# RXMIX.net
KiCad netlist of a schematic drawn in Altium Designer
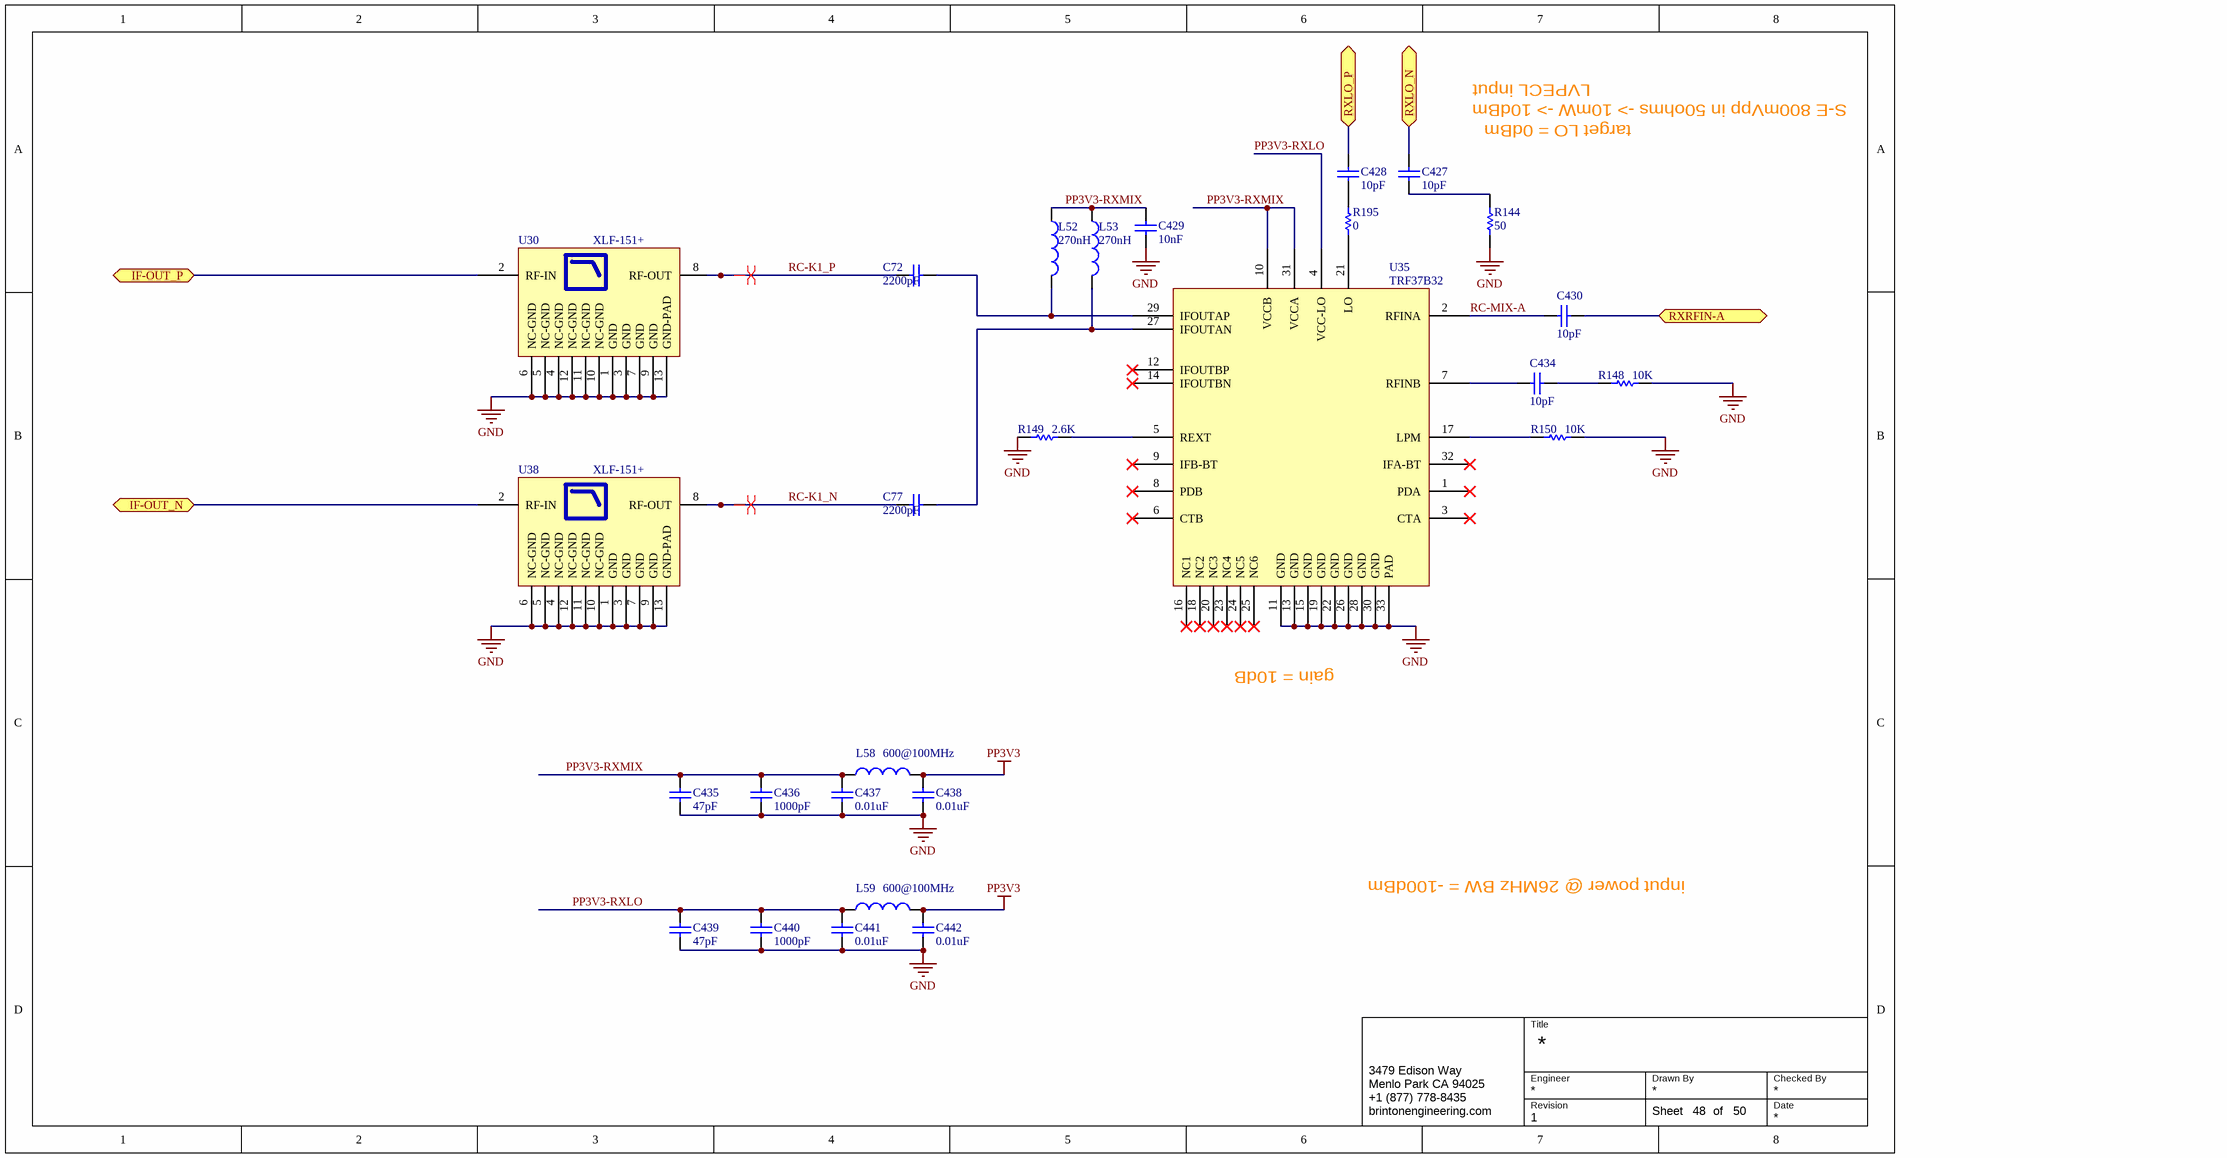
[diagram p0: RXMIX.SchDoc]

(export (version "E")
  (design (tool "Eeschema 10.0.6"))
  (components
    (comp (ref "C72")
      (value "2200pF")
      (footprint "0402")
      (description "CAP 0402")
      (fields (field (name "VOLTAGE") "50V") (field (name "MANUFACTURER") "Kemet"))
      (libsource (lib "PopRock") (part "CAP 0402"))
    )
    (comp (ref "C77")
      (value "2200pF")
      (footprint "0402")
      (description "CAP 0402")
      (fields (field (name "VOLTAGE") "50V") (field (name "MANUFACTURER") "Kemet"))
      (libsource (lib "PopRock") (part "CAP 0402"))
    )
    (comp (ref "C427")
      (value "10pF")
      (footprint "0402")
      (description "CAP 0402")
      (fields (field (name "VOLTAGE") "16V"))
      (libsource (lib "Graviton") (part "CAP 0402"))
    )
    (comp (ref "C428")
      (value "10pF")
      (footprint "0402")
      (description "CAP 0402")
      (fields (field (name "VOLTAGE") "16V"))
      (libsource (lib "Graviton") (part "CAP 0402"))
    )
    (comp (ref "C429")
      (value "10nF")
      (footprint "0402")
      (description "CAP 0402")
      (fields (field (name "VOLTAGE") "16V"))
      (libsource (lib "Graviton") (part "CAP 0402"))
    )
    (comp (ref "C430")
      (value "10pF")
      (footprint "0402")
      (description "CAP 0402")
      (fields (field (name "VOLTAGE") "16V"))
      (libsource (lib "Graviton") (part "CAP 0402"))
    )
    (comp (ref "C434")
      (value "10pF")
      (footprint "0402")
      (description "CAP 0402")
      (fields (field (name "VOLTAGE") "16V"))
      (libsource (lib "Graviton") (part "CAP 0402"))
    )
    (comp (ref "C435")
      (value "47pF")
      (footprint "0402")
      (description "CAP 0402")
      (fields (field (name "VOLTAGE") "25V") (field (name "MANUFACTURER") "Kemet"))
      (libsource (lib "Graviton") (part "CAP 0402"))
    )
    (comp (ref "C436")
      (value "1000pF")
      (footprint "0402")
      (description "CAP 0402")
      (fields (field (name "VOLTAGE") "50V") (field (name "MANUFACTURER") "Murata"))
      (libsource (lib "Graviton") (part "CAP 0402"))
    )
    (comp (ref "C437")
      (value "0.01uF")
      (footprint "0402")
      (description "CAP 0402")
      (fields (field (name "VOLTAGE") "25V") (field (name "MANUFACTURER") "Murata"))
      (libsource (lib "Graviton") (part "CAP 0402"))
    )
    (comp (ref "C438")
      (value "0.01uF")
      (footprint "0402")
      (description "CAP 0402")
      (fields (field (name "VOLTAGE") "25V") (field (name "MANUFACTURER") "Murata"))
      (libsource (lib "Graviton") (part "CAP 0402"))
    )
    (comp (ref "C439")
      (value "47pF")
      (footprint "0402")
      (description "CAP 0402")
      (fields (field (name "VOLTAGE") "25V") (field (name "MANUFACTURER") "Kemet"))
      (libsource (lib "Graviton") (part "CAP 0402"))
    )
    (comp (ref "C440")
      (value "1000pF")
      (footprint "0402")
      (description "CAP 0402")
      (fields (field (name "VOLTAGE") "50V") (field (name "MANUFACTURER") "Murata"))
      (libsource (lib "Graviton") (part "CAP 0402"))
    )
    (comp (ref "C441")
      (value "0.01uF")
      (footprint "0402")
      (description "CAP 0402")
      (fields (field (name "VOLTAGE") "25V") (field (name "MANUFACTURER") "Murata"))
      (libsource (lib "Graviton") (part "CAP 0402"))
    )
    (comp (ref "C442")
      (value "0.01uF")
      (footprint "0402")
      (description "CAP 0402")
      (fields (field (name "VOLTAGE") "25V") (field (name "MANUFACTURER") "Murata"))
      (libsource (lib "Graviton") (part "CAP 0402"))
    )
    (comp (ref "L52")
      (value "270nH")
      (footprint "0603")
      (description "Inductor")
      (fields (field (name "Comment") "IND 0603"))
      (libsource (lib "Graviton") (part "IND 0603"))
    )
    (comp (ref "L53")
      (value "270nH")
      (footprint "0603")
      (description "Inductor")
      (fields (field (name "Comment") "IND 0603"))
      (libsource (lib "Graviton") (part "IND 0603"))
    )
    (comp (ref "L58")
      (value "600@100MHz")
      (footprint "0402")
      (description "Inductor")
      (fields (field (name "MANUFACTURER") "Murata") (field (name "Comment") "IND 0402"))
      (libsource (lib "Graviton") (part "IND 0402"))
    )
    (comp (ref "L59")
      (value "600@100MHz")
      (footprint "0402")
      (description "Inductor")
      (fields (field (name "MANUFACTURER") "Murata") (field (name "Comment") "IND 0402"))
      (libsource (lib "Graviton") (part "IND 0402"))
    )
    (comp (ref "R144")
      (value "50")
      (footprint "0402")
      (description "Resistor, SMD 0402")
      (fields (field (name "Comment") "RES 0402"))
      (libsource (lib "Graviton") (part "RES 0402"))
    )
    (comp (ref "R148")
      (value "10K")
      (footprint "0402")
      (description "Resistor, SMD 0402")
      (fields (field (name "Comment") "RES 0402"))
      (libsource (lib "Graviton") (part "RES 0402"))
    )
    (comp (ref "R149")
      (value "2.6K")
      (footprint "0402")
      (description "Resistor, SMD 0402")
      (fields (field (name "Comment") "RES 0402"))
      (libsource (lib "Graviton") (part "RES 0402"))
    )
    (comp (ref "R150")
      (value "10K")
      (footprint "0402")
      (description "Resistor, SMD 0402")
      (fields (field (name "Comment") "RES 0402"))
      (libsource (lib "Graviton") (part "RES 0402"))
    )
    (comp (ref "R195")
      (value "0")
      (footprint "0402")
      (description "Resistor, SMD 0402")
      (fields (field (name "Comment") "RES 0402"))
      (libsource (lib "Graviton") (part "RES 0402"))
    )
    (comp (ref "U30")
      (value "XLF-151+")
      (footprint "QFN-XLF-12")
      (description "Reflectionless Low-Pass Filter, DC-150Mhz")
      (fields (field (name "MANUFACTURER") "Mini-Circuits"))
      (libsource (lib "Mini-Circuits") (part "XLF-151+"))
    )
    (comp (ref "U35")
      (value "TRF37B32")
      (footprint "RTV-WQFN-32")
      (description "Dual Downmixer,  500-3300MHz with IF Amp")
      (fields (field (name "MANUFACTURER") "Texas Instruments"))
      (libsource (lib "ti") (part "TRF37B32"))
    )
    (comp (ref "U38")
      (value "XLF-151+")
      (footprint "QFN-XLF-12")
      (description "Reflectionless Low-Pass Filter, DC-150Mhz")
      (fields (field (name "MANUFACTURER") "Mini-Circuits"))
      (libsource (lib "Mini-Circuits") (part "XLF-151+"))
    )
  )
  (nets
    (net (code "1") (name "/IF-OUT_N") (class "Default")
      (node (ref "U38") (pin "2") (pinfunction "RF-IN_2") (pintype "passive"))
    )
    (net (code "2") (name "/IF-OUT_P") (class "Default")
      (node (ref "U30") (pin "2") (pinfunction "RF-IN_2") (pintype "passive"))
    )
    (net (code "3") (name "/PP3V3-RXLO") (class "Default")
      (node (ref "C439") (pin "2") (pinfunction "2_2") (pintype "passive"))
      (node (ref "C440") (pin "2") (pinfunction "2_2") (pintype "passive"))
      (node (ref "C441") (pin "2") (pinfunction "2_2") (pintype "passive"))
      (node (ref "L59") (pin "2") (pinfunction "2_2") (pintype "passive"))
      (node (ref "U35") (pin "4") (pinfunction "VCC-LO_4") (pintype "passive"))
    )
    (net (code "4") (name "/PP3V3-RXMIX") (class "Default")
      (node (ref "C429") (pin "2") (pinfunction "2_2") (pintype "passive"))
      (node (ref "C435") (pin "2") (pinfunction "2_2") (pintype "passive"))
      (node (ref "C436") (pin "2") (pinfunction "2_2") (pintype "passive"))
      (node (ref "C437") (pin "2") (pinfunction "2_2") (pintype "passive"))
      (node (ref "L52") (pin "2") (pinfunction "2_2") (pintype "passive"))
      (node (ref "L53") (pin "2") (pinfunction "2_2") (pintype "passive"))
      (node (ref "L58") (pin "2") (pinfunction "2_2") (pintype "passive"))
      (node (ref "U35") (pin "10") (pinfunction "VCCB_10") (pintype "passive"))
      (node (ref "U35") (pin "31") (pinfunction "VCCA_31") (pintype "passive"))
    )
    (net (code "5") (name "/RC-K1_N") (class "Default")
      (node (ref "C77") (pin "2") (pinfunction "2_2") (pintype "passive"))
      (node (ref "U38") (pin "8") (pinfunction "RF-OUT_8") (pintype "passive"))
    )
    (net (code "6") (name "/RC-K1_P") (class "Default")
      (node (ref "C72") (pin "2") (pinfunction "2_2") (pintype "passive"))
      (node (ref "U30") (pin "8") (pinfunction "RF-OUT_8") (pintype "passive"))
    )
    (net (code "7") (name "/RC-MIX-A") (class "Default")
      (node (ref "C430") (pin "2") (pinfunction "2_2") (pintype "passive"))
      (node (ref "U35") (pin "2") (pinfunction "RFINA_2") (pintype "passive"))
    )
    (net (code "8") (name "/RXLO_N") (class "Default")
      (node (ref "C427") (pin "1") (pinfunction "1_1") (pintype "passive"))
    )
    (net (code "9") (name "/RXLO_P") (class "Default")
      (node (ref "C428") (pin "2") (pinfunction "2_2") (pintype "passive"))
    )
    (net (code "10") (name "/RXRFIN-A") (class "Default")
      (node (ref "C430") (pin "1") (pinfunction "1_1") (pintype "passive"))
    )
    (net (code "11") (name "GND") (class "Default")
      (node (ref "C429") (pin "1") (pinfunction "1_1") (pintype "passive"))
      (node (ref "C435") (pin "1") (pinfunction "1_1") (pintype "passive"))
      (node (ref "C436") (pin "1") (pinfunction "1_1") (pintype "passive"))
      (node (ref "C437") (pin "1") (pinfunction "1_1") (pintype "passive"))
      (node (ref "C438") (pin "1") (pinfunction "1_1") (pintype "passive"))
      (node (ref "C439") (pin "1") (pinfunction "1_1") (pintype "passive"))
      (node (ref "C440") (pin "1") (pinfunction "1_1") (pintype "passive"))
      (node (ref "C441") (pin "1") (pinfunction "1_1") (pintype "passive"))
      (node (ref "C442") (pin "1") (pinfunction "1_1") (pintype "passive"))
      (node (ref "R144") (pin "2") (pinfunction "2_2") (pintype "passive"))
      (node (ref "R148") (pin "1") (pinfunction "1_1") (pintype "passive"))
      (node (ref "R149") (pin "2") (pinfunction "2_2") (pintype "passive"))
      (node (ref "R150") (pin "1") (pinfunction "1_1") (pintype "passive"))
      (node (ref "U30") (pin "1") (pinfunction "GND_1") (pintype "passive"))
      (node (ref "U30") (pin "10") (pinfunction "NC-GND_10") (pintype "passive"))
      (node (ref "U30") (pin "11") (pinfunction "NC-GND_11") (pintype "passive"))
      (node (ref "U30") (pin "12") (pinfunction "NC-GND_12") (pintype "passive"))
      (node (ref "U30") (pin "13") (pinfunction "GND-PAD_13") (pintype "passive"))
      (node (ref "U30") (pin "3") (pinfunction "GND_3") (pintype "passive"))
      (node (ref "U30") (pin "4") (pinfunction "NC-GND_4") (pintype "passive"))
      (node (ref "U30") (pin "5") (pinfunction "NC-GND_5") (pintype "passive"))
      (node (ref "U30") (pin "6") (pinfunction "NC-GND_6") (pintype "passive"))
      (node (ref "U30") (pin "7") (pinfunction "GND_7") (pintype "passive"))
      (node (ref "U30") (pin "9") (pinfunction "GND_9") (pintype "passive"))
      (node (ref "U35") (pin "11") (pinfunction "GND_11") (pintype "passive"))
      (node (ref "U35") (pin "13") (pinfunction "GND_13") (pintype "passive"))
      (node (ref "U35") (pin "15") (pinfunction "GND_15") (pintype "passive"))
      (node (ref "U35") (pin "19") (pinfunction "GND_19") (pintype "passive"))
      (node (ref "U35") (pin "22") (pinfunction "GND_22") (pintype "passive"))
      (node (ref "U35") (pin "26") (pinfunction "GND_26") (pintype "passive"))
      (node (ref "U35") (pin "28") (pinfunction "GND_28") (pintype "passive"))
      (node (ref "U35") (pin "30") (pinfunction "GND_30") (pintype "passive"))
      (node (ref "U35") (pin "33") (pinfunction "PAD_33") (pintype "passive"))
      (node (ref "U38") (pin "1") (pinfunction "GND_1") (pintype "passive"))
      (node (ref "U38") (pin "10") (pinfunction "NC-GND_10") (pintype "passive"))
      (node (ref "U38") (pin "11") (pinfunction "NC-GND_11") (pintype "passive"))
      (node (ref "U38") (pin "12") (pinfunction "NC-GND_12") (pintype "passive"))
      (node (ref "U38") (pin "13") (pinfunction "GND-PAD_13") (pintype "passive"))
      (node (ref "U38") (pin "3") (pinfunction "GND_3") (pintype "passive"))
      (node (ref "U38") (pin "4") (pinfunction "NC-GND_4") (pintype "passive"))
      (node (ref "U38") (pin "5") (pinfunction "NC-GND_5") (pintype "passive"))
      (node (ref "U38") (pin "6") (pinfunction "NC-GND_6") (pintype "passive"))
      (node (ref "U38") (pin "7") (pinfunction "GND_7") (pintype "passive"))
      (node (ref "U38") (pin "9") (pinfunction "GND_9") (pintype "passive"))
    )
    (net (code "12") (name "Net-(C427-Pad2)") (class "Default")
      (node (ref "C427") (pin "2") (pinfunction "2_2") (pintype "passive"))
      (node (ref "R144") (pin "1") (pinfunction "1_1") (pintype "passive"))
    )
    (net (code "13") (name "Net-(C428-Pad1)") (class "Default")
      (node (ref "C428") (pin "1") (pinfunction "1_1") (pintype "passive"))
      (node (ref "R195") (pin "1") (pinfunction "1_1") (pintype "passive"))
    )
    (net (code "14") (name "Net-(C434-Pad1)") (class "Default")
      (node (ref "C434") (pin "1") (pinfunction "1_1") (pintype "passive"))
      (node (ref "R148") (pin "2") (pinfunction "2_2") (pintype "passive"))
    )
    (net (code "15") (name "Net-(U35-IFOUTAN)") (class "Default")
      (node (ref "C77") (pin "1") (pinfunction "1_1") (pintype "passive"))
      (node (ref "L53") (pin "1") (pinfunction "1_1") (pintype "passive"))
      (node (ref "U35") (pin "27") (pinfunction "IFOUTAN_27") (pintype "passive"))
    )
    (net (code "16") (name "Net-(U35-IFOUTAP)") (class "Default")
      (node (ref "C72") (pin "1") (pinfunction "1_1") (pintype "passive"))
      (node (ref "L52") (pin "1") (pinfunction "1_1") (pintype "passive"))
      (node (ref "U35") (pin "29") (pinfunction "IFOUTAP_29") (pintype "passive"))
    )
    (net (code "17") (name "Net-(U35-LO)") (class "Default")
      (node (ref "R195") (pin "2") (pinfunction "2_2") (pintype "passive"))
      (node (ref "U35") (pin "21") (pinfunction "LO_21") (pintype "passive"))
    )
    (net (code "18") (name "Net-(U35-LPM)") (class "Default")
      (node (ref "R150") (pin "2") (pinfunction "2_2") (pintype "passive"))
      (node (ref "U35") (pin "17") (pinfunction "LPM_17") (pintype "passive"))
    )
    (net (code "19") (name "Net-(U35-REXT)") (class "Default")
      (node (ref "R149") (pin "1") (pinfunction "1_1") (pintype "passive"))
      (node (ref "U35") (pin "5") (pinfunction "REXT_5") (pintype "passive"))
    )
    (net (code "20") (name "Net-(U35-RFINB)") (class "Default")
      (node (ref "C434") (pin "2") (pinfunction "2_2") (pintype "passive"))
      (node (ref "U35") (pin "7") (pinfunction "RFINB_7") (pintype "passive"))
    )
    (net (code "21") (name "PP3V3") (class "Default")
      (node (ref "C438") (pin "2") (pinfunction "2_2") (pintype "passive"))
      (node (ref "C442") (pin "2") (pinfunction "2_2") (pintype "passive"))
      (node (ref "L58") (pin "1") (pinfunction "1_1") (pintype "passive"))
      (node (ref "L59") (pin "1") (pinfunction "1_1") (pintype "passive"))
    )
    (net (code "22") (name "unconnected-(U35-CTA-Pad3)") (class "Default")
      (node (ref "U35") (pin "3") (pinfunction "CTA_3") (pintype "passive+no_connect"))
    )
    (net (code "23") (name "unconnected-(U35-CTB-Pad6)") (class "Default")
      (node (ref "U35") (pin "6") (pinfunction "CTB_6") (pintype "passive+no_connect"))
    )
    (net (code "24") (name "unconnected-(U35-IFA-BT-Pad32)") (class "Default")
      (node (ref "U35") (pin "32") (pinfunction "IFA-BT_32") (pintype "passive+no_connect"))
    )
    (net (code "25") (name "unconnected-(U35-IFB-BT-Pad9)") (class "Default")
      (node (ref "U35") (pin "9") (pinfunction "IFB-BT_9") (pintype "passive+no_connect"))
    )
    (net (code "26") (name "unconnected-(U35-IFOUTBN-Pad14)") (class "Default")
      (node (ref "U35") (pin "14") (pinfunction "IFOUTBN_14") (pintype "passive+no_connect"))
    )
    (net (code "27") (name "unconnected-(U35-IFOUTBP-Pad12)") (class "Default")
      (node (ref "U35") (pin "12") (pinfunction "IFOUTBP_12") (pintype "passive+no_connect"))
    )
    (net (code "28") (name "unconnected-(U35-NC1-Pad16)") (class "Default")
      (node (ref "U35") (pin "16") (pinfunction "NC1_16") (pintype "passive+no_connect"))
    )
    (net (code "29") (name "unconnected-(U35-NC2-Pad18)") (class "Default")
      (node (ref "U35") (pin "18") (pinfunction "NC2_18") (pintype "passive+no_connect"))
    )
    (net (code "30") (name "unconnected-(U35-NC3-Pad20)") (class "Default")
      (node (ref "U35") (pin "20") (pinfunction "NC3_20") (pintype "passive+no_connect"))
    )
    (net (code "31") (name "unconnected-(U35-NC4-Pad23)") (class "Default")
      (node (ref "U35") (pin "23") (pinfunction "NC4_23") (pintype "passive+no_connect"))
    )
    (net (code "32") (name "unconnected-(U35-NC5-Pad24)") (class "Default")
      (node (ref "U35") (pin "24") (pinfunction "NC5_24") (pintype "passive+no_connect"))
    )
    (net (code "33") (name "unconnected-(U35-NC6-Pad25)") (class "Default")
      (node (ref "U35") (pin "25") (pinfunction "NC6_25") (pintype "passive+no_connect"))
    )
    (net (code "34") (name "unconnected-(U35-PDA-Pad1)") (class "Default")
      (node (ref "U35") (pin "1") (pinfunction "PDA_1") (pintype "passive+no_connect"))
    )
    (net (code "35") (name "unconnected-(U35-PDB-Pad8)") (class "Default")
      (node (ref "U35") (pin "8") (pinfunction "PDB_8") (pintype "passive+no_connect"))
    )
  )
)
